# SparkFun-Photon-Wearable-Shield.net
KiCad netlist of a schematic drawn in EAGLE
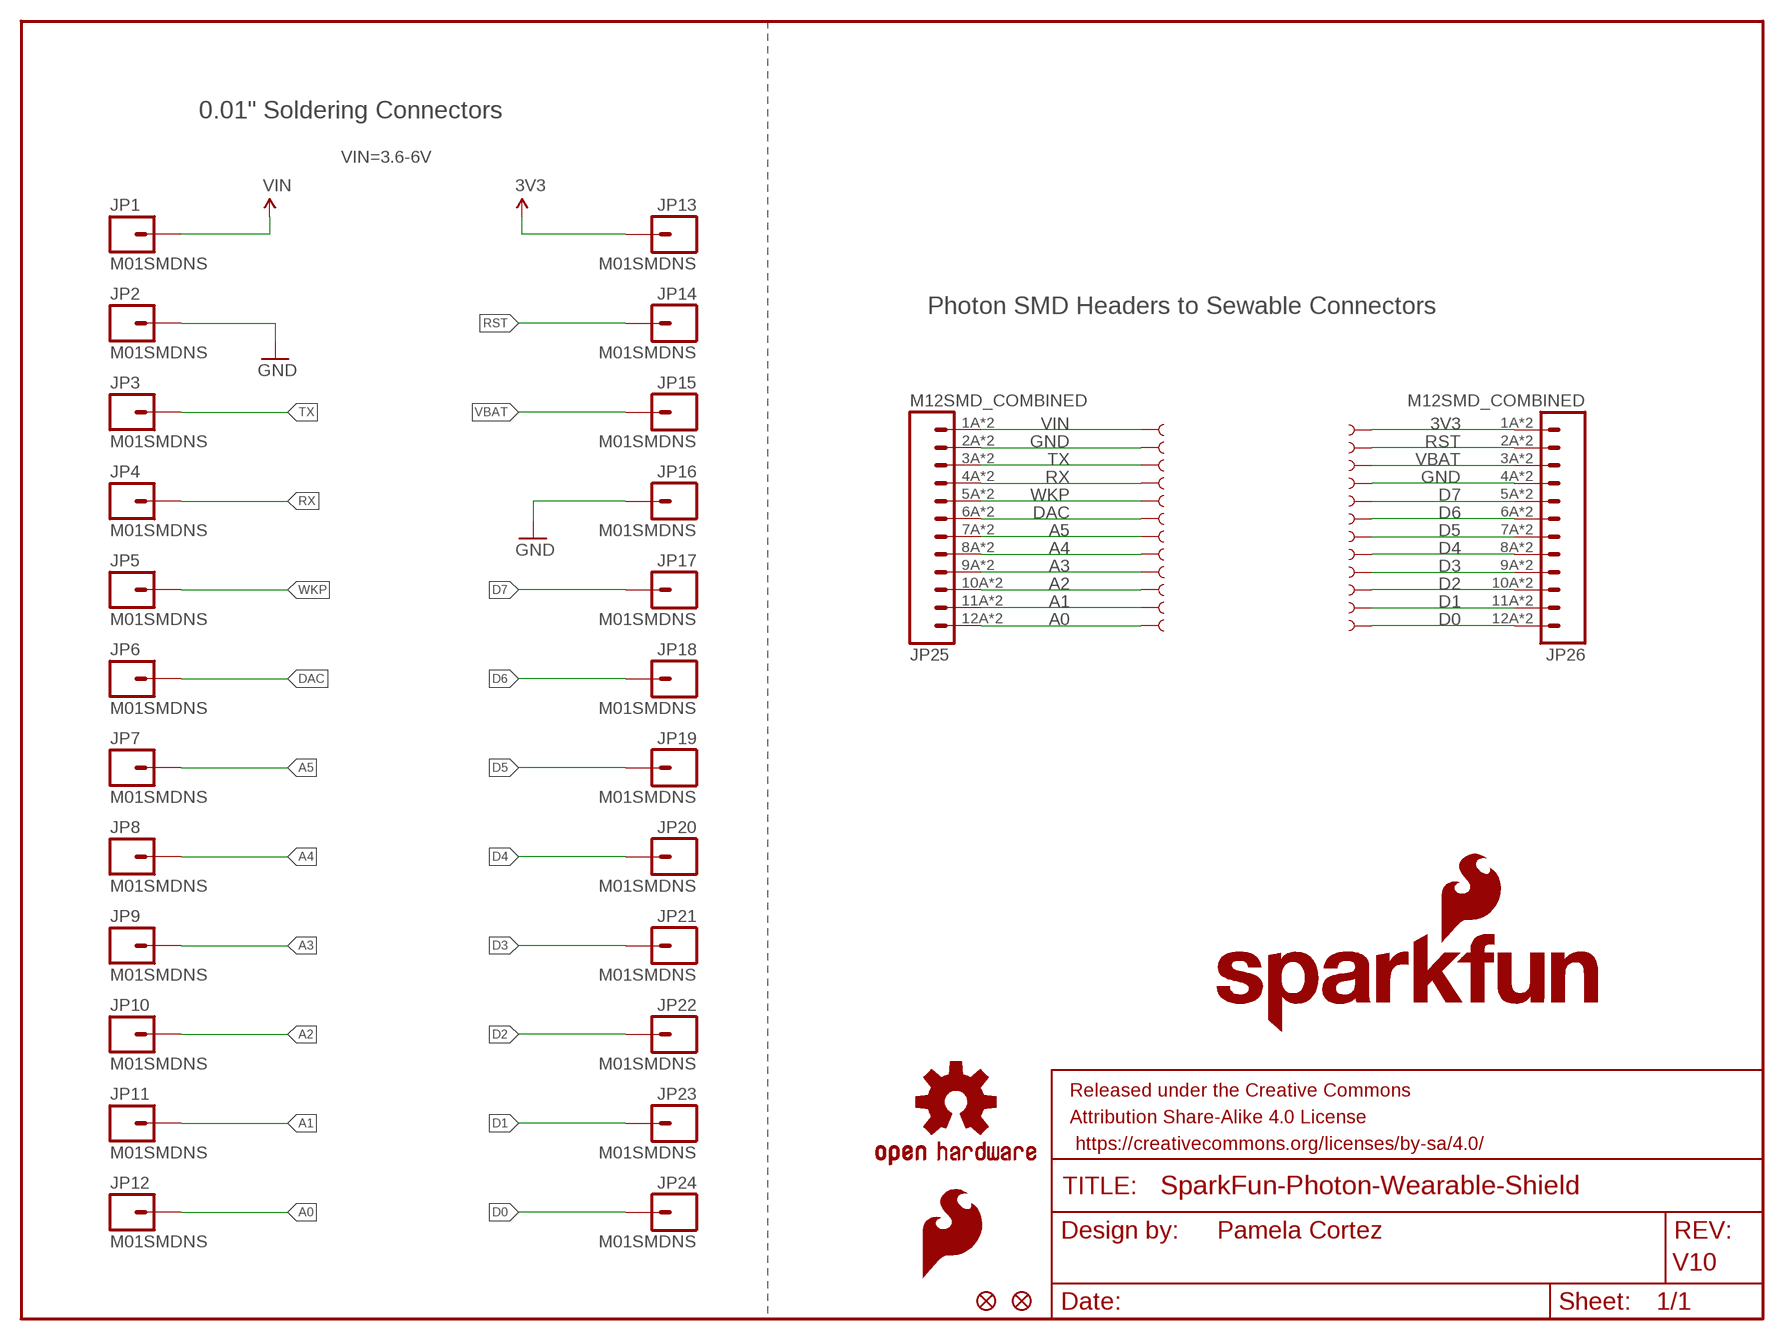
[diagram p0: schematic, sheet 1]

(export (version "E")
  (design (tool "Eeschema 10.0.6"))
  (components
    (comp (ref "FID1")
      (value "FIDUCIAL1X2")
      (footprint "eagle-import:FIDUCIAL-1X2")
      (libsource (lib "eagle-import") (part "FIDUCIAL1X2"))
    )
    (comp (ref "FID2")
      (value "FIDUCIAL1X2")
      (footprint "eagle-import:FIDUCIAL-1X2")
      (libsource (lib "eagle-import") (part "FIDUCIAL1X2"))
    )
    (comp (ref "FRAME1")
      (value "FRAME-LETTER")
      (footprint "eagle-import:CREATIVE_COMMONS")
      (fields (field (name "DESIGNER") "NAME"))
      (libsource (lib "eagle-import") (part "FRAME-LETTER"))
    )
    (comp (ref "J1")
      (value "PAD")
      (footprint "eagle-import:PAD-LONG-2-SIDED")
      (libsource (lib "eagle-import") (part "PAD"))
    )
    (comp (ref "J2")
      (value "PAD")
      (footprint "eagle-import:PAD-LONG-2-SIDED")
      (libsource (lib "eagle-import") (part "PAD"))
    )
    (comp (ref "J3")
      (value "PAD")
      (footprint "eagle-import:PAD-LONG-2-SIDED")
      (libsource (lib "eagle-import") (part "PAD"))
    )
    (comp (ref "J4")
      (value "PAD")
      (footprint "eagle-import:PAD-LONG-2-SIDED")
      (libsource (lib "eagle-import") (part "PAD"))
    )
    (comp (ref "J5")
      (value "PAD")
      (footprint "eagle-import:PAD-LONG-2-SIDED")
      (libsource (lib "eagle-import") (part "PAD"))
    )
    (comp (ref "J6")
      (value "PAD")
      (footprint "eagle-import:PAD-LONG-2-SIDED")
      (libsource (lib "eagle-import") (part "PAD"))
    )
    (comp (ref "J7")
      (value "PAD")
      (footprint "eagle-import:PAD-LONG-2-SIDED")
      (libsource (lib "eagle-import") (part "PAD"))
    )
    (comp (ref "J8")
      (value "PAD")
      (footprint "eagle-import:PAD-LONG-2-SIDED")
      (libsource (lib "eagle-import") (part "PAD"))
    )
    (comp (ref "J9")
      (value "PAD")
      (footprint "eagle-import:PAD-LONG-2-SIDED")
      (libsource (lib "eagle-import") (part "PAD"))
    )
    (comp (ref "J10")
      (value "PAD")
      (footprint "eagle-import:PAD-LONG-2-SIDED")
      (libsource (lib "eagle-import") (part "PAD"))
    )
    (comp (ref "J11")
      (value "PAD")
      (footprint "eagle-import:PAD-LONG-2-SIDED")
      (libsource (lib "eagle-import") (part "PAD"))
    )
    (comp (ref "J12")
      (value "PAD")
      (footprint "eagle-import:PAD-LONG-2-SIDED")
      (libsource (lib "eagle-import") (part "PAD"))
    )
    (comp (ref "J13")
      (value "PAD")
      (footprint "eagle-import:PAD-LONG-2-SIDED")
      (libsource (lib "eagle-import") (part "PAD"))
    )
    (comp (ref "J14")
      (value "PAD")
      (footprint "eagle-import:PAD-LONG-2-SIDED")
      (libsource (lib "eagle-import") (part "PAD"))
    )
    (comp (ref "J15")
      (value "PAD")
      (footprint "eagle-import:PAD-LONG-2-SIDED")
      (libsource (lib "eagle-import") (part "PAD"))
    )
    (comp (ref "J16")
      (value "PAD")
      (footprint "eagle-import:PAD-LONG-2-SIDED")
      (libsource (lib "eagle-import") (part "PAD"))
    )
    (comp (ref "J17")
      (value "PAD")
      (footprint "eagle-import:PAD-LONG-2-SIDED")
      (libsource (lib "eagle-import") (part "PAD"))
    )
    (comp (ref "J18")
      (value "PAD")
      (footprint "eagle-import:PAD-LONG-2-SIDED")
      (libsource (lib "eagle-import") (part "PAD"))
    )
    (comp (ref "J19")
      (value "PAD")
      (footprint "eagle-import:PAD-LONG-2-SIDED")
      (libsource (lib "eagle-import") (part "PAD"))
    )
    (comp (ref "J20")
      (value "PAD")
      (footprint "eagle-import:PAD-LONG-2-SIDED")
      (libsource (lib "eagle-import") (part "PAD"))
    )
    (comp (ref "J21")
      (value "PAD")
      (footprint "eagle-import:PAD-LONG-2-SIDED")
      (libsource (lib "eagle-import") (part "PAD"))
    )
    (comp (ref "J22")
      (value "PAD")
      (footprint "eagle-import:PAD-LONG-2-SIDED")
      (libsource (lib "eagle-import") (part "PAD"))
    )
    (comp (ref "J23")
      (value "PAD")
      (footprint "eagle-import:PAD-LONG-2-SIDED")
      (libsource (lib "eagle-import") (part "PAD"))
    )
    (comp (ref "J24")
      (value "PAD")
      (footprint "eagle-import:PAD-LONG-2-SIDED")
      (libsource (lib "eagle-import") (part "PAD"))
    )
    (comp (ref "JP1")
      (value "M01SMDNS")
      (footprint "eagle-import:1X01NS")
      (libsource (lib "eagle-import") (part "M01SMDNS"))
    )
    (comp (ref "JP2")
      (value "M01SMDNS")
      (footprint "eagle-import:1X01NS")
      (libsource (lib "eagle-import") (part "M01SMDNS"))
    )
    (comp (ref "JP3")
      (value "M01SMDNS")
      (footprint "eagle-import:1X01NS")
      (libsource (lib "eagle-import") (part "M01SMDNS"))
    )
    (comp (ref "JP4")
      (value "M01SMDNS")
      (footprint "eagle-import:1X01NS")
      (libsource (lib "eagle-import") (part "M01SMDNS"))
    )
    (comp (ref "JP5")
      (value "M01SMDNS")
      (footprint "eagle-import:1X01NS")
      (libsource (lib "eagle-import") (part "M01SMDNS"))
    )
    (comp (ref "JP6")
      (value "M01SMDNS")
      (footprint "eagle-import:1X01NS")
      (libsource (lib "eagle-import") (part "M01SMDNS"))
    )
    (comp (ref "JP7")
      (value "M01SMDNS")
      (footprint "eagle-import:1X01NS")
      (libsource (lib "eagle-import") (part "M01SMDNS"))
    )
    (comp (ref "JP8")
      (value "M01SMDNS")
      (footprint "eagle-import:1X01NS")
      (libsource (lib "eagle-import") (part "M01SMDNS"))
    )
    (comp (ref "JP9")
      (value "M01SMDNS")
      (footprint "eagle-import:1X01NS")
      (libsource (lib "eagle-import") (part "M01SMDNS"))
    )
    (comp (ref "JP10")
      (value "M01SMDNS")
      (footprint "eagle-import:1X01NS")
      (libsource (lib "eagle-import") (part "M01SMDNS"))
    )
    (comp (ref "JP11")
      (value "M01SMDNS")
      (footprint "eagle-import:1X01NS")
      (libsource (lib "eagle-import") (part "M01SMDNS"))
    )
    (comp (ref "JP12")
      (value "M01SMDNS")
      (footprint "eagle-import:1X01NS")
      (libsource (lib "eagle-import") (part "M01SMDNS"))
    )
    (comp (ref "JP13")
      (value "M01SMDNS")
      (footprint "eagle-import:1X01NS")
      (libsource (lib "eagle-import") (part "M01SMDNS"))
    )
    (comp (ref "JP14")
      (value "M01SMDNS")
      (footprint "eagle-import:1X01NS")
      (libsource (lib "eagle-import") (part "M01SMDNS"))
    )
    (comp (ref "JP15")
      (value "M01SMDNS")
      (footprint "eagle-import:1X01NS")
      (libsource (lib "eagle-import") (part "M01SMDNS"))
    )
    (comp (ref "JP16")
      (value "M01SMDNS")
      (footprint "eagle-import:1X01NS")
      (libsource (lib "eagle-import") (part "M01SMDNS"))
    )
    (comp (ref "JP17")
      (value "M01SMDNS")
      (footprint "eagle-import:1X01NS")
      (libsource (lib "eagle-import") (part "M01SMDNS"))
    )
    (comp (ref "JP18")
      (value "M01SMDNS")
      (footprint "eagle-import:1X01NS")
      (libsource (lib "eagle-import") (part "M01SMDNS"))
    )
    (comp (ref "JP19")
      (value "M01SMDNS")
      (footprint "eagle-import:1X01NS")
      (libsource (lib "eagle-import") (part "M01SMDNS"))
    )
    (comp (ref "JP20")
      (value "M01SMDNS")
      (footprint "eagle-import:1X01NS")
      (libsource (lib "eagle-import") (part "M01SMDNS"))
    )
    (comp (ref "JP21")
      (value "M01SMDNS")
      (footprint "eagle-import:1X01NS")
      (libsource (lib "eagle-import") (part "M01SMDNS"))
    )
    (comp (ref "JP22")
      (value "M01SMDNS")
      (footprint "eagle-import:1X01NS")
      (libsource (lib "eagle-import") (part "M01SMDNS"))
    )
    (comp (ref "JP23")
      (value "M01SMDNS")
      (footprint "eagle-import:1X01NS")
      (libsource (lib "eagle-import") (part "M01SMDNS"))
    )
    (comp (ref "JP24")
      (value "M01SMDNS")
      (footprint "eagle-import:1X01NS")
      (libsource (lib "eagle-import") (part "M01SMDNS"))
    )
    (comp (ref "JP25")
      (value "M12SMD_COMBINED")
      (footprint "eagle-import:1X12_SMD_COMBINED")
      (libsource (lib "eagle-import") (part "M12SMD_COMBINED"))
    )
    (comp (ref "JP26")
      (value "M12SMD_COMBINED")
      (footprint "eagle-import:1X12_SMD_COMBINED")
      (libsource (lib "eagle-import") (part "M12SMD_COMBINED"))
    )
    (comp (ref "LOGO1")
      (value "SFE_LOGO_FLAME.2_INCH")
      (footprint "eagle-import:SFE_LOGO_FLAME_.2")
      (libsource (lib "eagle-import") (part "SFE_LOGO_FLAME.2_INCH"))
    )
    (comp (ref "LOGO2")
      (value "OSHW-LOGOM")
      (footprint "eagle-import:OSHW-LOGO-M")
      (libsource (lib "eagle-import") (part "OSHW-LOGOM"))
    )
    (comp (ref "LOGO3")
      (value "SFE_LOGO_NAME_FLAME.1_INCH")
      (footprint "eagle-import:SFE_LOGO_NAME_FLAME_.1")
      (libsource (lib "eagle-import") (part "SFE_LOGO_NAME_FLAME.1_INCH"))
    )
  )
  (nets
    (net (code "1") (name "3V3") (class "Default")
      (node (ref "J13") (pin "1") (pinfunction "1_1") (pintype "bidirectional"))
      (node (ref "JP13") (pin "1") (pinfunction "1_1") (pintype "passive"))
      (node (ref "JP26") (pin "1A") (pinfunction "1_1A") (pintype "passive"))
      (node (ref "JP26") (pin "1B") (pinfunction "1_1B") (pintype "passive"))
    )
    (net (code "2") (name "A0") (class "Default")
      (node (ref "J12") (pin "1") (pinfunction "1_1") (pintype "bidirectional"))
      (node (ref "JP12") (pin "1") (pinfunction "1_1") (pintype "passive"))
      (node (ref "JP25") (pin "12A") (pinfunction "12_12A") (pintype "passive"))
      (node (ref "JP25") (pin "12B") (pinfunction "12_12B") (pintype "passive"))
    )
    (net (code "3") (name "A1") (class "Default")
      (node (ref "J11") (pin "1") (pinfunction "1_1") (pintype "bidirectional"))
      (node (ref "JP11") (pin "1") (pinfunction "1_1") (pintype "passive"))
      (node (ref "JP25") (pin "11A") (pinfunction "11_11A") (pintype "passive"))
      (node (ref "JP25") (pin "11B") (pinfunction "11_11B") (pintype "passive"))
    )
    (net (code "4") (name "A2") (class "Default")
      (node (ref "J10") (pin "1") (pinfunction "1_1") (pintype "bidirectional"))
      (node (ref "JP10") (pin "1") (pinfunction "1_1") (pintype "passive"))
      (node (ref "JP25") (pin "10A") (pinfunction "10_10A") (pintype "passive"))
      (node (ref "JP25") (pin "10B") (pinfunction "10_10B") (pintype "passive"))
    )
    (net (code "5") (name "A3") (class "Default")
      (node (ref "J9") (pin "1") (pinfunction "1_1") (pintype "bidirectional"))
      (node (ref "JP25") (pin "9A") (pinfunction "9_9A") (pintype "passive"))
      (node (ref "JP25") (pin "9B") (pinfunction "9_9B") (pintype "passive"))
      (node (ref "JP9") (pin "1") (pinfunction "1_1") (pintype "passive"))
    )
    (net (code "6") (name "A4") (class "Default")
      (node (ref "J8") (pin "1") (pinfunction "1_1") (pintype "bidirectional"))
      (node (ref "JP25") (pin "8A") (pinfunction "8_8A") (pintype "passive"))
      (node (ref "JP25") (pin "8B") (pinfunction "8_8B") (pintype "passive"))
      (node (ref "JP8") (pin "1") (pinfunction "1_1") (pintype "passive"))
    )
    (net (code "7") (name "A5") (class "Default")
      (node (ref "J7") (pin "1") (pinfunction "1_1") (pintype "bidirectional"))
      (node (ref "JP25") (pin "7A") (pinfunction "7_7A") (pintype "passive"))
      (node (ref "JP25") (pin "7B") (pinfunction "7_7B") (pintype "passive"))
      (node (ref "JP7") (pin "1") (pinfunction "1_1") (pintype "passive"))
    )
    (net (code "8") (name "D0") (class "Default")
      (node (ref "J24") (pin "1") (pinfunction "1_1") (pintype "bidirectional"))
      (node (ref "JP24") (pin "1") (pinfunction "1_1") (pintype "passive"))
      (node (ref "JP26") (pin "12A") (pinfunction "12_12A") (pintype "passive"))
      (node (ref "JP26") (pin "12B") (pinfunction "12_12B") (pintype "passive"))
    )
    (net (code "9") (name "D1") (class "Default")
      (node (ref "J23") (pin "1") (pinfunction "1_1") (pintype "bidirectional"))
      (node (ref "JP23") (pin "1") (pinfunction "1_1") (pintype "passive"))
      (node (ref "JP26") (pin "11A") (pinfunction "11_11A") (pintype "passive"))
      (node (ref "JP26") (pin "11B") (pinfunction "11_11B") (pintype "passive"))
    )
    (net (code "10") (name "D2") (class "Default")
      (node (ref "J22") (pin "1") (pinfunction "1_1") (pintype "bidirectional"))
      (node (ref "JP22") (pin "1") (pinfunction "1_1") (pintype "passive"))
      (node (ref "JP26") (pin "10A") (pinfunction "10_10A") (pintype "passive"))
      (node (ref "JP26") (pin "10B") (pinfunction "10_10B") (pintype "passive"))
    )
    (net (code "11") (name "D3") (class "Default")
      (node (ref "J21") (pin "1") (pinfunction "1_1") (pintype "bidirectional"))
      (node (ref "JP21") (pin "1") (pinfunction "1_1") (pintype "passive"))
      (node (ref "JP26") (pin "9A") (pinfunction "9_9A") (pintype "passive"))
      (node (ref "JP26") (pin "9B") (pinfunction "9_9B") (pintype "passive"))
    )
    (net (code "12") (name "D4") (class "Default")
      (node (ref "J20") (pin "1") (pinfunction "1_1") (pintype "bidirectional"))
      (node (ref "JP20") (pin "1") (pinfunction "1_1") (pintype "passive"))
      (node (ref "JP26") (pin "8A") (pinfunction "8_8A") (pintype "passive"))
      (node (ref "JP26") (pin "8B") (pinfunction "8_8B") (pintype "passive"))
    )
    (net (code "13") (name "D5") (class "Default")
      (node (ref "J19") (pin "1") (pinfunction "1_1") (pintype "bidirectional"))
      (node (ref "JP19") (pin "1") (pinfunction "1_1") (pintype "passive"))
      (node (ref "JP26") (pin "7A") (pinfunction "7_7A") (pintype "passive"))
      (node (ref "JP26") (pin "7B") (pinfunction "7_7B") (pintype "passive"))
    )
    (net (code "14") (name "D6") (class "Default")
      (node (ref "J18") (pin "1") (pinfunction "1_1") (pintype "bidirectional"))
      (node (ref "JP18") (pin "1") (pinfunction "1_1") (pintype "passive"))
      (node (ref "JP26") (pin "6A") (pinfunction "6_6A") (pintype "passive"))
      (node (ref "JP26") (pin "6B") (pinfunction "6_6B") (pintype "passive"))
    )
    (net (code "15") (name "D7") (class "Default")
      (node (ref "J17") (pin "1") (pinfunction "1_1") (pintype "bidirectional"))
      (node (ref "JP17") (pin "1") (pinfunction "1_1") (pintype "passive"))
      (node (ref "JP26") (pin "5A") (pinfunction "5_5A") (pintype "passive"))
      (node (ref "JP26") (pin "5B") (pinfunction "5_5B") (pintype "passive"))
    )
    (net (code "16") (name "DAC") (class "Default")
      (node (ref "J6") (pin "1") (pinfunction "1_1") (pintype "bidirectional"))
      (node (ref "JP25") (pin "6A") (pinfunction "6_6A") (pintype "passive"))
      (node (ref "JP25") (pin "6B") (pinfunction "6_6B") (pintype "passive"))
      (node (ref "JP6") (pin "1") (pinfunction "1_1") (pintype "passive"))
    )
    (net (code "17") (name "GND") (class "Default")
      (node (ref "J16") (pin "1") (pinfunction "1_1") (pintype "bidirectional"))
      (node (ref "J2") (pin "1") (pinfunction "1_1") (pintype "bidirectional"))
      (node (ref "JP16") (pin "1") (pinfunction "1_1") (pintype "passive"))
      (node (ref "JP2") (pin "1") (pinfunction "1_1") (pintype "passive"))
      (node (ref "JP25") (pin "2A") (pinfunction "2_2A") (pintype "passive"))
      (node (ref "JP25") (pin "2B") (pinfunction "2_2B") (pintype "passive"))
      (node (ref "JP26") (pin "4A") (pinfunction "4_4A") (pintype "passive"))
      (node (ref "JP26") (pin "4B") (pinfunction "4_4B") (pintype "passive"))
    )
    (net (code "18") (name "RST") (class "Default")
      (node (ref "J14") (pin "1") (pinfunction "1_1") (pintype "bidirectional"))
      (node (ref "JP14") (pin "1") (pinfunction "1_1") (pintype "passive"))
      (node (ref "JP26") (pin "2A") (pinfunction "2_2A") (pintype "passive"))
      (node (ref "JP26") (pin "2B") (pinfunction "2_2B") (pintype "passive"))
    )
    (net (code "19") (name "RX") (class "Default")
      (node (ref "J4") (pin "1") (pinfunction "1_1") (pintype "bidirectional"))
      (node (ref "JP25") (pin "4A") (pinfunction "4_4A") (pintype "passive"))
      (node (ref "JP25") (pin "4B") (pinfunction "4_4B") (pintype "passive"))
      (node (ref "JP4") (pin "1") (pinfunction "1_1") (pintype "passive"))
    )
    (net (code "20") (name "TX") (class "Default")
      (node (ref "J3") (pin "1") (pinfunction "1_1") (pintype "bidirectional"))
      (node (ref "JP25") (pin "3A") (pinfunction "3_3A") (pintype "passive"))
      (node (ref "JP25") (pin "3B") (pinfunction "3_3B") (pintype "passive"))
      (node (ref "JP3") (pin "1") (pinfunction "1_1") (pintype "passive"))
    )
    (net (code "21") (name "VBAT") (class "Default")
      (node (ref "J15") (pin "1") (pinfunction "1_1") (pintype "bidirectional"))
      (node (ref "JP15") (pin "1") (pinfunction "1_1") (pintype "passive"))
      (node (ref "JP26") (pin "3A") (pinfunction "3_3A") (pintype "passive"))
      (node (ref "JP26") (pin "3B") (pinfunction "3_3B") (pintype "passive"))
    )
    (net (code "22") (name "VIN") (class "Default")
      (node (ref "J1") (pin "1") (pinfunction "1_1") (pintype "bidirectional"))
      (node (ref "JP1") (pin "1") (pinfunction "1_1") (pintype "passive"))
      (node (ref "JP25") (pin "1A") (pinfunction "1_1A") (pintype "passive"))
      (node (ref "JP25") (pin "1B") (pinfunction "1_1B") (pintype "passive"))
    )
    (net (code "23") (name "WKP") (class "Default")
      (node (ref "J5") (pin "1") (pinfunction "1_1") (pintype "bidirectional"))
      (node (ref "JP25") (pin "5A") (pinfunction "5_5A") (pintype "passive"))
      (node (ref "JP25") (pin "5B") (pinfunction "5_5B") (pintype "passive"))
      (node (ref "JP5") (pin "1") (pinfunction "1_1") (pintype "passive"))
    )
  )
)
